# RELAY19.net
KiCad netlist of a schematic drawn in Altium Designer
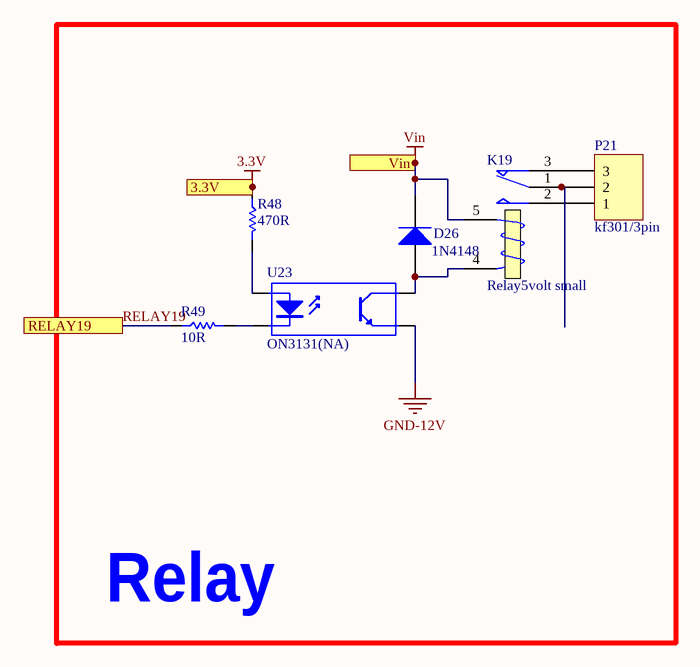
[diagram p0: RELAY19.SchDoc]

(export (version "E")
  (design (tool "Eeschema 10.0.6"))
  (components
    (comp (ref "D26")
      (value "1N4148")
      (footprint "sod123")
      (description "1 Amp General Purpose Rectifier")
      (fields (field (name "PUBLISHER") "Altium Limited"))
      (libsource (lib "Miscellaneous Devices") (part "Diode 1N4007"))
    )
    (comp (ref "K19")
      (value "Relay5volt small")
      (footprint "relay5_childern")
      (description "SPDT Relay")
      (fields (field (name "PUBLISHER") "Altium Limited"))
      (libsource (lib "FLIB") (part "Relay"))
    )
    (comp (ref "P21")
      (value "kf301/3pin")
      (footprint "Blue Connector 1*3 -kf301")
      (fields (field (name "PUBLISHER") "Altium Limited"))
      (libsource (lib "Miscellaneous Connectors") (part "Header 3"))
    )
    (comp (ref "R48")
      (value "470R")
      (footprint "0805/resistor")
      (description "Resistor")
      (fields (field (name "TOLERANCE") "5%") (field (name "POWER") "1/8 W"))
      (libsource (lib "skille") (part "Resistor"))
    )
    (comp (ref "R49")
      (value "10R")
      (footprint "0805/resistor")
      (description "Resistor")
      (fields (field (name "TOLERANCE") "5%") (field (name "POWER") "1/8 W"))
      (libsource (lib "skille") (part "Resistor"))
    )
    (comp (ref "U23")
      (value "ON3131(NA)")
      (footprint "OPTO_COUPLER")
      (description "4-Pin Phototransistor Optocoupler")
      (fields (field (name "PUBLISHER") "Altium Limited"))
      (libsource (lib "skille") (part "Optoisolator1"))
    )
  )
  (nets
    (net (code "1") (name "/RELAY19") (class "Default")
      (node (ref "R49") (pin "1") (pinfunction "1_1") (pintype "passive"))
    )
    (net (code "2") (name "3.3V") (class "Default")
      (node (ref "R48") (pin "1") (pinfunction "1_1") (pintype "passive"))
    )
    (net (code "3") (name "GND-12V") (class "Default")
      (node (ref "U23") (pin "3") (pinfunction "E_3") (pintype "passive"))
    )
    (net (code "4") (name "Net-(K19-COM)") (class "Default")
      (node (ref "K19") (pin "1") (pinfunction "COM_1") (pintype "passive"))
      (node (ref "P21") (pin "2") (pinfunction "2_2") (pintype "passive"))
    )
    (net (code "5") (name "Net-(K19-NO)") (class "Default")
      (node (ref "K19") (pin "2") (pinfunction "NO_2") (pintype "passive"))
      (node (ref "P21") (pin "1") (pinfunction "1_1") (pintype "passive"))
    )
    (net (code "6") (name "Net-(K19-T1)") (class "Default")
      (node (ref "K19") (pin "3") (pinfunction "T1_3") (pintype "passive"))
      (node (ref "P21") (pin "3") (pinfunction "3_3") (pintype "passive"))
    )
    (net (code "7") (name "Net-(K19-T2)") (class "Default")
      (node (ref "D26") (pin "A") (pinfunction "A_A") (pintype "passive"))
      (node (ref "K19") (pin "4") (pinfunction "T2_4") (pintype "passive"))
      (node (ref "U23") (pin "4") (pinfunction "C_4") (pintype "passive"))
    )
    (net (code "8") (name "Net-(U23-A)") (class "Default")
      (node (ref "R48") (pin "2") (pinfunction "2_2") (pintype "passive"))
      (node (ref "U23") (pin "1") (pinfunction "A_1") (pintype "passive"))
    )
    (net (code "9") (name "Net-(U23-K)") (class "Default")
      (node (ref "R49") (pin "2") (pinfunction "2_2") (pintype "passive"))
      (node (ref "U23") (pin "2") (pinfunction "K_2") (pintype "passive"))
    )
    (net (code "10") (name "Vin") (class "Default")
      (node (ref "D26") (pin "K") (pinfunction "K_K") (pintype "passive"))
      (node (ref "K19") (pin "5") (pinfunction "5_5") (pintype "passive"))
    )
  )
)
